# Accelerometer_3-AXIS_-_BMA180.net
KiCad netlist of a schematic drawn in Altium Designer
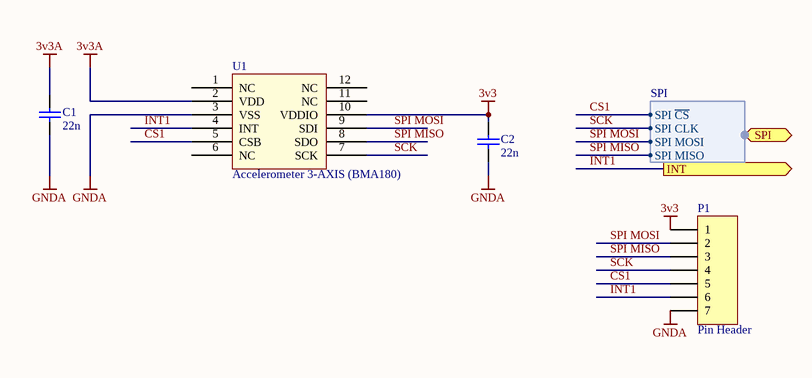
[diagram p0: Accelerometer 3-AXIS - BMA180.SchDoc]

(export (version "E")
  (design (tool "Eeschema 10.0.6"))
  (components
    (comp (ref "C1")
      (value "22n")
      (footprint "C0805")
      (fields (field (name "TOLERANCE") "0.1") (field (name "AUTHOR") "Willy Pietersz"))
      (libsource (lib "OurDb") (part "cap_NonPolar"))
    )
    (comp (ref "C2")
      (value "22n")
      (footprint "C0805")
      (fields (field (name "TOLERANCE") "0.1") (field (name "AUTHOR") "Willy Pietersz"))
      (libsource (lib "OurDb") (part "cap_NonPolar"))
    )
    (comp (ref "P1")
      (value "Pin Header")
      (footprint "PH1x7_2.54")
      (description "Con1x7")
      (fields (field (name "PART NUMBER") "PH1x7") (field (name "AUTHOR") "Willy Pietersz"))
      (libsource (lib "OurDb") (part "Con1x7"))
    )
    (comp (ref "U1")
      (value "Accelerometer 3-AXIS (BMA180)")
      (footprint "BMA180")
      (fields (field (name "PART NUMBER") "BMA180"))
      (libsource (lib "OurDb") (part "BMA180"))
    )
  )
  (nets
    (net (code "2") (name "/CS1") (class "Default")
      (node (ref "P1") (pin "5") (pinfunction "5_5") (pintype "passive"))
      (node (ref "U1") (pin "5") (pinfunction "CSB_5") (pintype "passive"))
    )
    (net (code "3") (name "/INT1") (class "Default")
      (node (ref "P1") (pin "6") (pinfunction "6_6") (pintype "passive"))
      (node (ref "U1") (pin "4") (pinfunction "INT_4") (pintype "passive"))
    )
    (net (code "4") (name "/SCK") (class "Default")
      (node (ref "P1") (pin "4") (pinfunction "4_4") (pintype "passive"))
      (node (ref "U1") (pin "7") (pinfunction "SCK_7") (pintype "passive"))
    )
    (net (code "5") (name "/SPI MISO") (class "Default")
      (node (ref "P1") (pin "3") (pinfunction "3_3") (pintype "passive"))
      (node (ref "U1") (pin "8") (pinfunction "SDO_8") (pintype "passive"))
    )
    (net (code "6") (name "/SPI MOSI") (class "Default")
      (node (ref "P1") (pin "2") (pinfunction "2_2") (pintype "passive"))
      (node (ref "U1") (pin "9") (pinfunction "SDI_9") (pintype "passive"))
    )
    (net (code "8") (name "3v3") (class "Default")
      (node (ref "C2") (pin "2") (pinfunction "2_2") (pintype "passive"))
      (node (ref "P1") (pin "1") (pinfunction "1_1") (pintype "passive"))
      (node (ref "U1") (pin "10") (pinfunction "VDDIO_10") (pintype "passive"))
    )
    (net (code "9") (name "3v3A") (class "Default")
      (node (ref "C1") (pin "2") (pinfunction "2_2") (pintype "passive"))
      (node (ref "U1") (pin "2") (pinfunction "VDD_2") (pintype "passive"))
    )
    (net (code "10") (name "GNDA") (class "Default")
      (node (ref "C1") (pin "1") (pinfunction "1_1") (pintype "passive"))
      (node (ref "C2") (pin "1") (pinfunction "1_1") (pintype "passive"))
      (node (ref "P1") (pin "7") (pinfunction "7_7") (pintype "passive"))
      (node (ref "U1") (pin "3") (pinfunction "VSS_3") (pintype "passive"))
    )
    (net (code "11") (name "unconnected-(U1-NC-Pad1)") (class "Default")
      (node (ref "U1") (pin "1") (pinfunction "NC_1") (pintype "passive"))
    )
    (net (code "12") (name "unconnected-(U1-NC-Pad6)") (class "Default")
      (node (ref "U1") (pin "6") (pinfunction "NC_6") (pintype "passive"))
    )
    (net (code "13") (name "unconnected-(U1-NC-Pad11)") (class "Default")
      (node (ref "U1") (pin "11") (pinfunction "NC_11") (pintype "passive"))
    )
    (net (code "14") (name "unconnected-(U1-NC-Pad12)") (class "Default")
      (node (ref "U1") (pin "12") (pinfunction "NC_12") (pintype "passive"))
    )
  )
)
